# ttl_net_fast_and.net
KiCad netlist of a schematic drawn in EAGLE
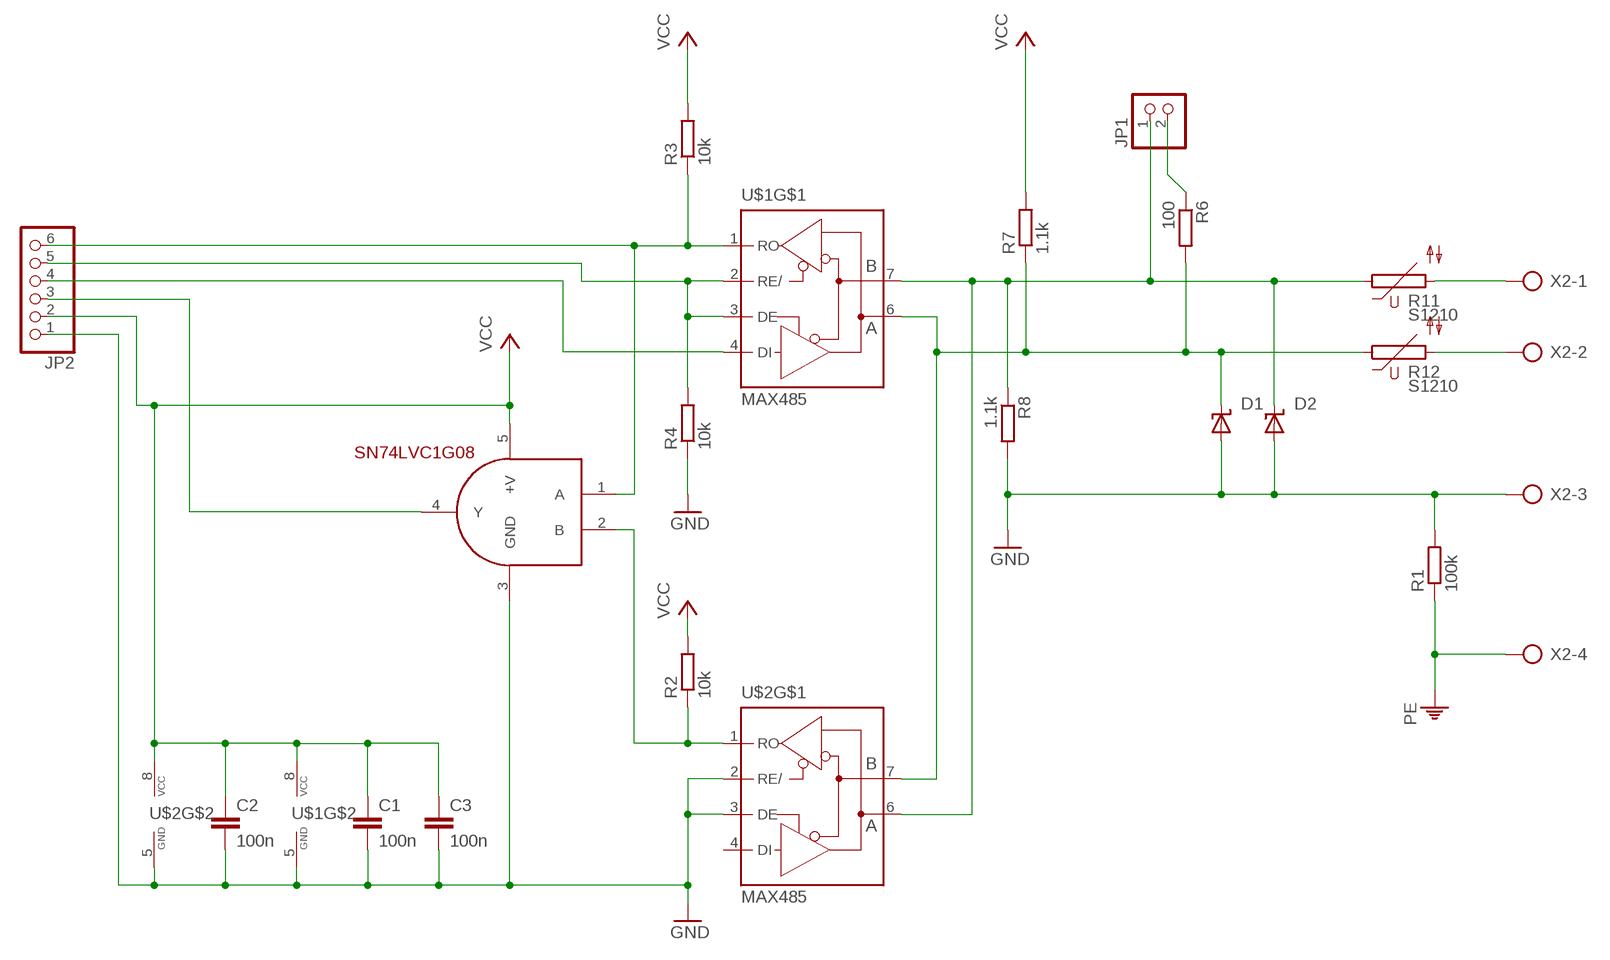
[diagram p0: schematic, sheet 1]

(export (version "E")
  (design (tool "Eeschema 10.0.6"))
  (components
    (comp (ref "C1")
      (value "100n")
      (footprint "eagle-import:C050-035X075")
      (libsource (lib "eagle-import") (part "C-EU050-035X075"))
    )
    (comp (ref "C2")
      (value "100n")
      (footprint "eagle-import:C050-035X075")
      (libsource (lib "eagle-import") (part "C-EU050-035X075"))
    )
    (comp (ref "C3")
      (value "100n")
      (footprint "eagle-import:C1206")
      (libsource (lib "eagle-import") (part "C-EUC1206"))
    )
    (comp (ref "D1")
      (value "SUPPRESSOR-SMBJ")
      (footprint "eagle-import:SMBJ")
      (libsource (lib "eagle-import") (part "SUPPRESSOR-SMBJ"))
    )
    (comp (ref "D2")
      (value "SUPPRESSOR-SMBJ")
      (footprint "eagle-import:SMBJ")
      (libsource (lib "eagle-import") (part "SUPPRESSOR-SMBJ"))
    )
    (comp (ref "JP1")
      (value "PINHD-1X2")
      (footprint "eagle-import:1X02")
      (libsource (lib "eagle-import") (part "PINHD-1X2"))
    )
    (comp (ref "JP2")
      (value "PINHD-1X6")
      (footprint "eagle-import:1X06")
      (libsource (lib "eagle-import") (part "PINHD-1X6"))
    )
    (comp (ref "R1")
      (value "100k")
      (footprint "eagle-import:0204_7")
      (libsource (lib "eagle-import") (part "resistor_R-EU_0204/7"))
    )
    (comp (ref "R2")
      (value "10k")
      (footprint "eagle-import:R1206")
      (libsource (lib "eagle-import") (part "R-EU_R1206"))
    )
    (comp (ref "R3")
      (value "10k")
      (footprint "eagle-import:R1206")
      (libsource (lib "eagle-import") (part "R-EU_R1206"))
    )
    (comp (ref "R4")
      (value "10k")
      (footprint "eagle-import:R1206")
      (libsource (lib "eagle-import") (part "R-EU_R1206"))
    )
    (comp (ref "R6")
      (value "100")
      (footprint "eagle-import:0204_7")
      (libsource (lib "eagle-import") (part "resistor_R-EU_0204/7"))
    )
    (comp (ref "R7")
      (value "1.1k")
      (footprint "eagle-import:0204_7")
      (libsource (lib "eagle-import") (part "resistor_R-EU_0204/7"))
    )
    (comp (ref "R8")
      (value "1.1k")
      (footprint "eagle-import:0204_7")
      (libsource (lib "eagle-import") (part "resistor_R-EU_0204/7"))
    )
    (comp (ref "R11")
      (value "S1210")
      (footprint "eagle-import:S1210")
      (libsource (lib "eagle-import") (part "S1210"))
    )
    (comp (ref "R12")
      (value "S1210")
      (footprint "eagle-import:S1210")
      (libsource (lib "eagle-import") (part "S1210"))
    )
    (comp (ref "U$1")
      (value "MAX485")
      (footprint "eagle-import:DIL08")
      (libsource (lib "eagle-import") (part "MAX485"))
    )
    (comp (ref "U$2")
      (value "MAX485")
      (footprint "eagle-import:DIL08")
      (libsource (lib "eagle-import") (part "MAX485"))
    )
    (comp (ref "U$3")
      (value "SN74LVC1G08")
      (footprint "eagle-import:SOT23-5")
      (libsource (lib "eagle-import") (part "SN74LVC1G08"))
    )
    (comp (ref "X2")
      (value "AK500/4")
      (footprint "eagle-import:AK500_4")
      (libsource (lib "eagle-import") (part "AK500/4"))
    )
  )
  (nets
    (net (code "1") (name "GND") (class "Default")
      (node (ref "C1") (pin "2") (pinfunction "2_2") (pintype "passive"))
      (node (ref "C2") (pin "2") (pinfunction "2_2") (pintype "passive"))
      (node (ref "C3") (pin "2") (pinfunction "2_2") (pintype "passive"))
      (node (ref "D1") (pin "A") (pinfunction "A_A") (pintype "passive"))
      (node (ref "D2") (pin "A") (pinfunction "A_A") (pintype "passive"))
      (node (ref "JP2") (pin "1") (pinfunction "1_1") (pintype "passive"))
      (node (ref "R1") (pin "2") (pinfunction "2_2") (pintype "passive"))
      (node (ref "R4") (pin "1") (pinfunction "1_1") (pintype "passive"))
      (node (ref "R8") (pin "2") (pinfunction "2_2") (pintype "passive"))
      (node (ref "U$1") (pin "5") (pinfunction "GND_5") (pintype "power_in"))
      (node (ref "U$2") (pin "2") (pinfunction "RE/_2") (pintype "input"))
      (node (ref "U$2") (pin "3") (pinfunction "DE_3") (pintype "input"))
      (node (ref "U$2") (pin "5") (pinfunction "GND_5") (pintype "power_in"))
      (node (ref "U$3") (pin "3") (pinfunction "GND_3") (pintype "bidirectional"))
      (node (ref "X2") (pin "3") (pinfunction "KL_3") (pintype "passive"))
    )
    (net (code "2") (name "Net-(JP1-Pad2)") (class "Default")
      (node (ref "JP1") (pin "2") (pinfunction "2_2") (pintype "passive"))
      (node (ref "R6") (pin "1") (pinfunction "1_1") (pintype "passive"))
    )
    (net (code "3") (name "Net-(U$1A-A)") (class "Default")
      (node (ref "D1") (pin "C") (pinfunction "C_C") (pintype "passive"))
      (node (ref "R12") (pin "1") (pinfunction "1_1") (pintype "passive"))
      (node (ref "R6") (pin "2") (pinfunction "2_2") (pintype "passive"))
      (node (ref "R7") (pin "1") (pinfunction "1_1") (pintype "passive"))
      (node (ref "U$1") (pin "6") (pinfunction "A_6") (pintype "passive"))
      (node (ref "U$2") (pin "7") (pinfunction "B_7") (pintype "passive"))
    )
    (net (code "4") (name "Net-(U$1A-B)") (class "Default")
      (node (ref "D2") (pin "C") (pinfunction "C_C") (pintype "passive"))
      (node (ref "JP1") (pin "1") (pinfunction "1_1") (pintype "passive"))
      (node (ref "R11") (pin "1") (pinfunction "1_1") (pintype "passive"))
      (node (ref "R8") (pin "1") (pinfunction "1_1") (pintype "passive"))
      (node (ref "U$1") (pin "7") (pinfunction "B_7") (pintype "passive"))
      (node (ref "U$2") (pin "6") (pinfunction "A_6") (pintype "passive"))
    )
    (net (code "5") (name "Net-(U$1A-DE)") (class "Default")
      (node (ref "JP2") (pin "5") (pinfunction "5_5") (pintype "passive"))
      (node (ref "R4") (pin "2") (pinfunction "2_2") (pintype "passive"))
      (node (ref "U$1") (pin "2") (pinfunction "RE/_2") (pintype "input"))
      (node (ref "U$1") (pin "3") (pinfunction "DE_3") (pintype "input"))
    )
    (net (code "6") (name "Net-(U$1A-DI)") (class "Default")
      (node (ref "JP2") (pin "4") (pinfunction "4_4") (pintype "passive"))
      (node (ref "U$1") (pin "4") (pinfunction "DI_4") (pintype "input"))
    )
    (net (code "7") (name "Net-(U$1A-RO)") (class "Default")
      (node (ref "JP2") (pin "6") (pinfunction "6_6") (pintype "passive"))
      (node (ref "R3") (pin "1") (pinfunction "1_1") (pintype "passive"))
      (node (ref "U$1") (pin "1") (pinfunction "RO_1") (pintype "output"))
      (node (ref "U$3") (pin "1") (pinfunction "A_1") (pintype "bidirectional"))
    )
    (net (code "8") (name "Net-(U$2A-RO)") (class "Default")
      (node (ref "R2") (pin "1") (pinfunction "1_1") (pintype "passive"))
      (node (ref "U$2") (pin "1") (pinfunction "RO_1") (pintype "output"))
      (node (ref "U$3") (pin "2") (pinfunction "B_2") (pintype "bidirectional"))
    )
    (net (code "9") (name "Net-(U$3-Y)") (class "Default")
      (node (ref "JP2") (pin "3") (pinfunction "3_3") (pintype "passive"))
      (node (ref "U$3") (pin "4") (pinfunction "Y_4") (pintype "bidirectional"))
    )
    (net (code "10") (name "Net-(X2A-KL)") (class "Default")
      (node (ref "R11") (pin "2") (pinfunction "2_2") (pintype "passive"))
      (node (ref "X2") (pin "1") (pinfunction "KL_1") (pintype "passive"))
    )
    (net (code "11") (name "Net-(X2B-KL)") (class "Default")
      (node (ref "R12") (pin "2") (pinfunction "2_2") (pintype "passive"))
      (node (ref "X2") (pin "2") (pinfunction "KL_2") (pintype "passive"))
    )
    (net (code "12") (name "PE") (class "Default")
      (node (ref "R1") (pin "1") (pinfunction "1_1") (pintype "passive"))
      (node (ref "X2") (pin "4") (pinfunction "KL_4") (pintype "passive"))
    )
    (net (code "13") (name "VCC") (class "Default")
      (node (ref "C1") (pin "1") (pinfunction "1_1") (pintype "passive"))
      (node (ref "C2") (pin "1") (pinfunction "1_1") (pintype "passive"))
      (node (ref "C3") (pin "1") (pinfunction "1_1") (pintype "passive"))
      (node (ref "JP2") (pin "2") (pinfunction "2_2") (pintype "passive"))
      (node (ref "R2") (pin "2") (pinfunction "2_2") (pintype "passive"))
      (node (ref "R3") (pin "2") (pinfunction "2_2") (pintype "passive"))
      (node (ref "R7") (pin "2") (pinfunction "2_2") (pintype "passive"))
      (node (ref "U$1") (pin "8") (pinfunction "VCC_8") (pintype "power_in"))
      (node (ref "U$2") (pin "8") (pinfunction "VCC_8") (pintype "power_in"))
      (node (ref "U$3") (pin "5") (pinfunction "+V_5") (pintype "bidirectional"))
    )
    (net (code "14") (name "unconnected-(U$2A-DI-Pad4)") (class "Default")
      (node (ref "U$2") (pin "4") (pinfunction "DI_4") (pintype "input"))
    )
  )
)
